# pcg_eletr.net
KiCad netlist of a schematic drawn in EAGLE
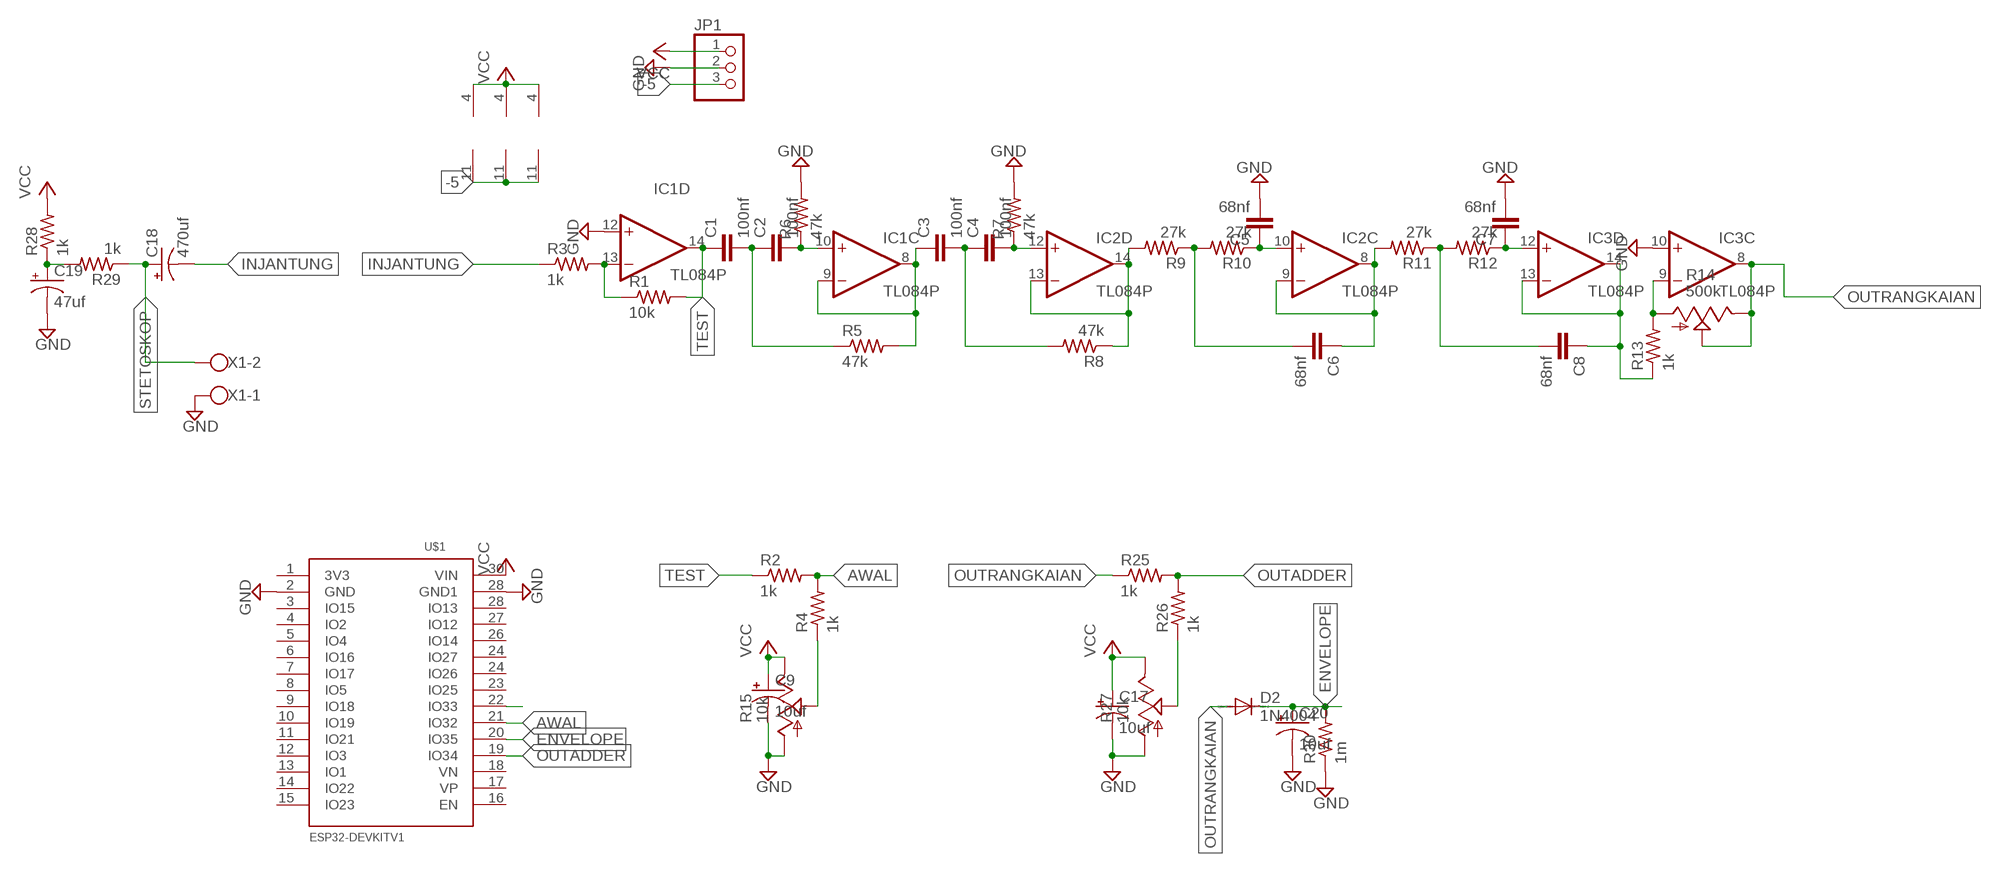
[diagram p0: schematic, sheet 1]

(export (version "E")
  (design (tool "Eeschema 10.0.6"))
  (components
    (comp (ref "C1")
      (value "100nf")
      (footprint "eagle-import:C050-025X075")
      (libsource (lib "eagle-import") (part "C-EU050-025X075"))
    )
    (comp (ref "C2")
      (value "100nf")
      (footprint "eagle-import:C050-025X075")
      (libsource (lib "eagle-import") (part "C-EU050-025X075"))
    )
    (comp (ref "C3")
      (value "100nf")
      (footprint "eagle-import:C050-025X075")
      (libsource (lib "eagle-import") (part "C-EU050-025X075"))
    )
    (comp (ref "C4")
      (value "100nf")
      (footprint "eagle-import:C050-025X075")
      (libsource (lib "eagle-import") (part "C-EU050-025X075"))
    )
    (comp (ref "C5")
      (value "68nf")
      (footprint "eagle-import:C050-025X075")
      (libsource (lib "eagle-import") (part "C-EU050-025X075"))
    )
    (comp (ref "C6")
      (value "68nf")
      (footprint "eagle-import:C050-025X075")
      (libsource (lib "eagle-import") (part "C-EU050-025X075"))
    )
    (comp (ref "C7")
      (value "68nf")
      (footprint "eagle-import:C050-025X075")
      (libsource (lib "eagle-import") (part "C-EU050-025X075"))
    )
    (comp (ref "C8")
      (value "68nf")
      (footprint "eagle-import:C050-025X075")
      (libsource (lib "eagle-import") (part "C-EU050-025X075"))
    )
    (comp (ref "C9")
      (value "10uf")
      (footprint "eagle-import:E2-5")
      (libsource (lib "eagle-import") (part "CPOL-USE2-5"))
    )
    (comp (ref "C17")
      (value "10uf")
      (footprint "eagle-import:E2-5")
      (libsource (lib "eagle-import") (part "CPOL-USE2-5"))
    )
    (comp (ref "C18")
      (value "470uf")
      (footprint "eagle-import:E2,5-7")
      (libsource (lib "eagle-import") (part "CPOL-USE2.5-7"))
    )
    (comp (ref "C19")
      (value "47uf")
      (footprint "eagle-import:E2-5")
      (libsource (lib "eagle-import") (part "CPOL-USE2-5"))
    )
    (comp (ref "C20")
      (value "10uf")
      (footprint "eagle-import:E2-5")
      (libsource (lib "eagle-import") (part "CPOL-USE2-5"))
    )
    (comp (ref "D2")
      (value "1N4004")
      (footprint "eagle-import:DO41-10")
      (libsource (lib "eagle-import") (part "1N4004"))
    )
    (comp (ref "IC1")
      (value "TL084P")
      (footprint "eagle-import:DIL14")
      (libsource (lib "eagle-import") (part "TL084P"))
    )
    (comp (ref "IC2")
      (value "TL084P")
      (footprint "eagle-import:DIL14")
      (libsource (lib "eagle-import") (part "TL084P"))
    )
    (comp (ref "IC3")
      (value "TL084P")
      (footprint "eagle-import:DIL14")
      (libsource (lib "eagle-import") (part "TL084P"))
    )
    (comp (ref "JP1")
      (value "PINHD-1X3")
      (footprint "eagle-import:1X03")
      (libsource (lib "eagle-import") (part "PINHD-1X3"))
    )
    (comp (ref "R1")
      (value "10k")
      (footprint "eagle-import:0207_7")
      (libsource (lib "eagle-import") (part "R-US_0207/7"))
    )
    (comp (ref "R2")
      (value "1k")
      (footprint "eagle-import:0207_7")
      (libsource (lib "eagle-import") (part "R-US_0207/7"))
    )
    (comp (ref "R3")
      (value "1k")
      (footprint "eagle-import:0207_7")
      (libsource (lib "eagle-import") (part "R-US_0207/7"))
    )
    (comp (ref "R4")
      (value "1k")
      (footprint "eagle-import:0207_7")
      (libsource (lib "eagle-import") (part "R-US_0207/7"))
    )
    (comp (ref "R5")
      (value "47k")
      (footprint "eagle-import:0207_7")
      (libsource (lib "eagle-import") (part "R-US_0207/7"))
    )
    (comp (ref "R6")
      (value "47k")
      (footprint "eagle-import:0207_7")
      (libsource (lib "eagle-import") (part "R-US_0207/7"))
    )
    (comp (ref "R7")
      (value "47k")
      (footprint "eagle-import:0207_7")
      (libsource (lib "eagle-import") (part "R-US_0207/7"))
    )
    (comp (ref "R8")
      (value "47k")
      (footprint "eagle-import:0207_7")
      (libsource (lib "eagle-import") (part "R-US_0207/7"))
    )
    (comp (ref "R9")
      (value "27k")
      (footprint "eagle-import:0207_7")
      (libsource (lib "eagle-import") (part "R-US_0207/7"))
    )
    (comp (ref "R10")
      (value "27k")
      (footprint "eagle-import:0207_7")
      (libsource (lib "eagle-import") (part "R-US_0207/7"))
    )
    (comp (ref "R11")
      (value "27k")
      (footprint "eagle-import:0207_7")
      (libsource (lib "eagle-import") (part "R-US_0207/7"))
    )
    (comp (ref "R12")
      (value "27k")
      (footprint "eagle-import:0207_7")
      (libsource (lib "eagle-import") (part "R-US_0207/7"))
    )
    (comp (ref "R13")
      (value "1k")
      (footprint "eagle-import:0207_7")
      (libsource (lib "eagle-import") (part "R-US_0207/7"))
    )
    (comp (ref "R14")
      (value "500k")
      (footprint "eagle-import:B64Y")
      (libsource (lib "eagle-import") (part "TRIM_US-B64Y"))
    )
    (comp (ref "R15")
      (value "10k")
      (footprint "eagle-import:B64Y")
      (libsource (lib "eagle-import") (part "TRIM_US-B64Y"))
    )
    (comp (ref "R25")
      (value "1k")
      (footprint "eagle-import:0207_7")
      (libsource (lib "eagle-import") (part "R-US_0207/7"))
    )
    (comp (ref "R26")
      (value "1k")
      (footprint "eagle-import:0207_7")
      (libsource (lib "eagle-import") (part "R-US_0207/7"))
    )
    (comp (ref "R27")
      (value "10k")
      (footprint "eagle-import:B64Y")
      (libsource (lib "eagle-import") (part "TRIM_US-B64Y"))
    )
    (comp (ref "R28")
      (value "1k")
      (footprint "eagle-import:0207_7")
      (libsource (lib "eagle-import") (part "R-US_0207/7"))
    )
    (comp (ref "R29")
      (value "1k")
      (footprint "eagle-import:0207_7")
      (libsource (lib "eagle-import") (part "R-US_0207/7"))
    )
    (comp (ref "R30")
      (value "1m")
      (footprint "eagle-import:0207_7")
      (libsource (lib "eagle-import") (part "R-US_0207/7"))
    )
    (comp (ref "U$1")
      (value "ESP32DEVKITV1")
      (footprint "eagle-import:ESP32-DEVKITV1")
      (libsource (lib "eagle-import") (part "ESP32DEVKITV1"))
    )
    (comp (ref "X1")
      (value "W237-102")
      (footprint "eagle-import:W237-102")
      (fields (field (name "MPN") "237-102"))
      (libsource (lib "eagle-import") (part "W237-102"))
    )
  )
  (nets
    (net (code "1") (name "-5") (class "Default")
      (node (ref "IC1") (pin "11") (pinfunction "V-_11") (pintype "power_in"))
      (node (ref "IC2") (pin "11") (pinfunction "V-_11") (pintype "power_in"))
      (node (ref "IC3") (pin "11") (pinfunction "V-_11") (pintype "power_in"))
      (node (ref "JP1") (pin "3") (pinfunction "3_3") (pintype "passive"))
    )
    (net (code "2") (name "AWAL") (class "Default")
      (node (ref "R2") (pin "2") (pinfunction "2_2") (pintype "passive"))
      (node (ref "R4") (pin "2") (pinfunction "2_2") (pintype "passive"))
      (node (ref "U$1") (pin "21") (pinfunction "IO32_21") (pintype "bidirectional"))
    )
    (net (code "3") (name "ENVELOPE") (class "Default")
      (node (ref "C20") (pin "+") (pinfunction "+_+") (pintype "passive"))
      (node (ref "D2") (pin "C") (pinfunction "C_C") (pintype "passive"))
      (node (ref "R30") (pin "2") (pinfunction "2_2") (pintype "passive"))
      (node (ref "U$1") (pin "20") (pinfunction "IO35_20") (pintype "bidirectional"))
    )
    (net (code "4") (name "GND") (class "Default")
      (node (ref "C17") (pin "-") (pinfunction "-_-") (pintype "passive"))
      (node (ref "C19") (pin "-") (pinfunction "-_-") (pintype "passive"))
      (node (ref "C20") (pin "-") (pinfunction "-_-") (pintype "passive"))
      (node (ref "C5") (pin "2") (pinfunction "2_2") (pintype "passive"))
      (node (ref "C7") (pin "2") (pinfunction "2_2") (pintype "passive"))
      (node (ref "C9") (pin "-") (pinfunction "-_-") (pintype "passive"))
      (node (ref "IC1") (pin "12") (pinfunction "+IN_12") (pintype "input"))
      (node (ref "IC3") (pin "10") (pinfunction "+IN_10") (pintype "input"))
      (node (ref "JP1") (pin "2") (pinfunction "2_2") (pintype "passive"))
      (node (ref "R15") (pin "A") (pinfunction "A_A") (pintype "passive"))
      (node (ref "R27") (pin "A") (pinfunction "A_A") (pintype "passive"))
      (node (ref "R30") (pin "1") (pinfunction "1_1") (pintype "passive"))
      (node (ref "R6") (pin "2") (pinfunction "2_2") (pintype "passive"))
      (node (ref "R7") (pin "2") (pinfunction "2_2") (pintype "passive"))
      (node (ref "U$1") (pin "2") (pinfunction "GND_2") (pintype "bidirectional"))
      (node (ref "U$1") (pin "28") (pinfunction "GND1_28") (pintype "bidirectional"))
      (node (ref "X1") (pin "1") (pinfunction "KL_1") (pintype "passive"))
    )
    (net (code "5") (name "INJANTUNG") (class "Default")
      (node (ref "C18") (pin "-") (pinfunction "-_-") (pintype "passive"))
      (node (ref "R3") (pin "1") (pinfunction "1_1") (pintype "passive"))
    )
    (net (code "6") (name "Net-(C1-Pad2)") (class "Default")
      (node (ref "C1") (pin "2") (pinfunction "2_2") (pintype "passive"))
      (node (ref "C2") (pin "1") (pinfunction "1_1") (pintype "passive"))
      (node (ref "R5") (pin "1") (pinfunction "1_1") (pintype "passive"))
    )
    (net (code "7") (name "Net-(C3-Pad2)") (class "Default")
      (node (ref "C3") (pin "2") (pinfunction "2_2") (pintype "passive"))
      (node (ref "C4") (pin "1") (pinfunction "1_1") (pintype "passive"))
      (node (ref "R8") (pin "2") (pinfunction "2_2") (pintype "passive"))
    )
    (net (code "8") (name "Net-(C6-Pad2)") (class "Default")
      (node (ref "C6") (pin "2") (pinfunction "2_2") (pintype "passive"))
      (node (ref "R10") (pin "2") (pinfunction "2_2") (pintype "passive"))
      (node (ref "R9") (pin "1") (pinfunction "1_1") (pintype "passive"))
    )
    (net (code "9") (name "Net-(C8-Pad2)") (class "Default")
      (node (ref "C8") (pin "2") (pinfunction "2_2") (pintype "passive"))
      (node (ref "R11") (pin "1") (pinfunction "1_1") (pintype "passive"))
      (node (ref "R12") (pin "2") (pinfunction "2_2") (pintype "passive"))
    )
    (net (code "10") (name "Net-(C19-Pad+)") (class "Default")
      (node (ref "C19") (pin "+") (pinfunction "+_+") (pintype "passive"))
      (node (ref "R28") (pin "1") (pinfunction "1_1") (pintype "passive"))
      (node (ref "R29") (pin "2") (pinfunction "2_2") (pintype "passive"))
    )
    (net (code "11") (name "Net-(IC1C-+IN)") (class "Default")
      (node (ref "C2") (pin "2") (pinfunction "2_2") (pintype "passive"))
      (node (ref "IC1") (pin "10") (pinfunction "+IN_10") (pintype "input"))
      (node (ref "R6") (pin "1") (pinfunction "1_1") (pintype "passive"))
    )
    (net (code "12") (name "Net-(IC1C--IN)") (class "Default")
      (node (ref "C3") (pin "1") (pinfunction "1_1") (pintype "passive"))
      (node (ref "IC1") (pin "8") (pinfunction "OUT_8") (pintype "output"))
      (node (ref "IC1") (pin "9") (pinfunction "-IN_9") (pintype "input"))
      (node (ref "R5") (pin "2") (pinfunction "2_2") (pintype "passive"))
    )
    (net (code "13") (name "Net-(IC1D--IN)") (class "Default")
      (node (ref "IC1") (pin "13") (pinfunction "-IN_13") (pintype "input"))
      (node (ref "R1") (pin "1") (pinfunction "1_1") (pintype "passive"))
      (node (ref "R3") (pin "2") (pinfunction "2_2") (pintype "passive"))
    )
    (net (code "14") (name "Net-(IC2C-+IN)") (class "Default")
      (node (ref "C5") (pin "1") (pinfunction "1_1") (pintype "passive"))
      (node (ref "IC2") (pin "10") (pinfunction "+IN_10") (pintype "input"))
      (node (ref "R10") (pin "1") (pinfunction "1_1") (pintype "passive"))
    )
    (net (code "15") (name "Net-(IC2C--IN)") (class "Default")
      (node (ref "C6") (pin "1") (pinfunction "1_1") (pintype "passive"))
      (node (ref "IC2") (pin "8") (pinfunction "OUT_8") (pintype "output"))
      (node (ref "IC2") (pin "9") (pinfunction "-IN_9") (pintype "input"))
      (node (ref "R11") (pin "2") (pinfunction "2_2") (pintype "passive"))
    )
    (net (code "16") (name "Net-(IC2D-+IN)") (class "Default")
      (node (ref "C4") (pin "2") (pinfunction "2_2") (pintype "passive"))
      (node (ref "IC2") (pin "12") (pinfunction "+IN_12") (pintype "input"))
      (node (ref "R7") (pin "1") (pinfunction "1_1") (pintype "passive"))
    )
    (net (code "17") (name "Net-(IC2D--IN)") (class "Default")
      (node (ref "IC2") (pin "13") (pinfunction "-IN_13") (pintype "input"))
      (node (ref "IC2") (pin "14") (pinfunction "OUT_14") (pintype "output"))
      (node (ref "R8") (pin "1") (pinfunction "1_1") (pintype "passive"))
      (node (ref "R9") (pin "2") (pinfunction "2_2") (pintype "passive"))
    )
    (net (code "18") (name "Net-(IC3C--IN)") (class "Default")
      (node (ref "IC3") (pin "9") (pinfunction "-IN_9") (pintype "input"))
      (node (ref "R13") (pin "2") (pinfunction "2_2") (pintype "passive"))
      (node (ref "R14") (pin "A") (pinfunction "A_A") (pintype "passive"))
    )
    (net (code "19") (name "Net-(IC3D-+IN)") (class "Default")
      (node (ref "C7") (pin "1") (pinfunction "1_1") (pintype "passive"))
      (node (ref "IC3") (pin "12") (pinfunction "+IN_12") (pintype "input"))
      (node (ref "R12") (pin "1") (pinfunction "1_1") (pintype "passive"))
    )
    (net (code "20") (name "Net-(IC3D--IN)") (class "Default")
      (node (ref "C8") (pin "1") (pinfunction "1_1") (pintype "passive"))
      (node (ref "IC3") (pin "13") (pinfunction "-IN_13") (pintype "input"))
      (node (ref "IC3") (pin "14") (pinfunction "OUT_14") (pintype "output"))
      (node (ref "R13") (pin "1") (pinfunction "1_1") (pintype "passive"))
    )
    (net (code "21") (name "Net-(R15-PadS)") (class "Default")
      (node (ref "R15") (pin "S") (pinfunction "S_S") (pintype "passive"))
      (node (ref "R4") (pin "1") (pinfunction "1_1") (pintype "passive"))
    )
    (net (code "22") (name "Net-(R26-Pad1)") (class "Default")
      (node (ref "R26") (pin "1") (pinfunction "1_1") (pintype "passive"))
      (node (ref "R27") (pin "S") (pinfunction "S_S") (pintype "passive"))
    )
    (net (code "23") (name "OUTADDER") (class "Default")
      (node (ref "R25") (pin "2") (pinfunction "2_2") (pintype "passive"))
      (node (ref "R26") (pin "2") (pinfunction "2_2") (pintype "passive"))
      (node (ref "U$1") (pin "19") (pinfunction "IO34_19") (pintype "bidirectional"))
    )
    (net (code "24") (name "OUTRANGKAIAN") (class "Default")
      (node (ref "D2") (pin "A") (pinfunction "A_A") (pintype "passive"))
      (node (ref "IC3") (pin "8") (pinfunction "OUT_8") (pintype "output"))
      (node (ref "R14") (pin "E") (pinfunction "E_E") (pintype "passive"))
      (node (ref "R14") (pin "S") (pinfunction "S_S") (pintype "passive"))
      (node (ref "R25") (pin "1") (pinfunction "1_1") (pintype "passive"))
    )
    (net (code "25") (name "STETOSKOP") (class "Default")
      (node (ref "C18") (pin "+") (pinfunction "+_+") (pintype "passive"))
      (node (ref "R29") (pin "1") (pinfunction "1_1") (pintype "passive"))
      (node (ref "X1") (pin "2") (pinfunction "KL_2") (pintype "passive"))
    )
    (net (code "26") (name "TEST") (class "Default")
      (node (ref "C1") (pin "1") (pinfunction "1_1") (pintype "passive"))
      (node (ref "IC1") (pin "14") (pinfunction "OUT_14") (pintype "output"))
      (node (ref "R1") (pin "2") (pinfunction "2_2") (pintype "passive"))
      (node (ref "R2") (pin "1") (pinfunction "1_1") (pintype "passive"))
    )
    (net (code "27") (name "VCC") (class "Default")
      (node (ref "C17") (pin "+") (pinfunction "+_+") (pintype "passive"))
      (node (ref "C9") (pin "+") (pinfunction "+_+") (pintype "passive"))
      (node (ref "IC1") (pin "4") (pinfunction "V+_4") (pintype "power_in"))
      (node (ref "IC2") (pin "4") (pinfunction "V+_4") (pintype "power_in"))
      (node (ref "IC3") (pin "4") (pinfunction "V+_4") (pintype "power_in"))
      (node (ref "JP1") (pin "1") (pinfunction "1_1") (pintype "passive"))
      (node (ref "R15") (pin "E") (pinfunction "E_E") (pintype "passive"))
      (node (ref "R27") (pin "E") (pinfunction "E_E") (pintype "passive"))
      (node (ref "R28") (pin "2") (pinfunction "2_2") (pintype "passive"))
      (node (ref "U$1") (pin "30") (pinfunction "VIN_30") (pintype "bidirectional"))
    )
    (net (code "28") (name "unconnected-(U$1-3V3-Pad1)") (class "Default")
      (node (ref "U$1") (pin "1") (pinfunction "3V3_1") (pintype "bidirectional"))
    )
    (net (code "29") (name "unconnected-(U$1-EN-Pad16)") (class "Default")
      (node (ref "U$1") (pin "16") (pinfunction "EN_16") (pintype "bidirectional"))
    )
    (net (code "30") (name "unconnected-(U$1-IO1-Pad13)") (class "Default")
      (node (ref "U$1") (pin "13") (pinfunction "IO1_13") (pintype "bidirectional"))
    )
    (net (code "31") (name "unconnected-(U$1-IO2-Pad4)") (class "Default")
      (node (ref "U$1") (pin "4") (pinfunction "IO2_4") (pintype "bidirectional"))
    )
    (net (code "32") (name "unconnected-(U$1-IO3-Pad12)") (class "Default")
      (node (ref "U$1") (pin "12") (pinfunction "IO3_12") (pintype "bidirectional"))
    )
    (net (code "33") (name "unconnected-(U$1-IO4-Pad5)") (class "Default")
      (node (ref "U$1") (pin "5") (pinfunction "IO4_5") (pintype "bidirectional"))
    )
    (net (code "34") (name "unconnected-(U$1-IO5-Pad8)") (class "Default")
      (node (ref "U$1") (pin "8") (pinfunction "IO5_8") (pintype "bidirectional"))
    )
    (net (code "35") (name "unconnected-(U$1-IO12-Pad27)") (class "Default")
      (node (ref "U$1") (pin "27") (pinfunction "IO12_27") (pintype "bidirectional"))
    )
    (net (code "36") (name "unconnected-(U$1-IO13-Pad28)") (class "Default")
      (node (ref "U$1") (pin "28") (pinfunction "IO13_28") (pintype "bidirectional"))
    )
    (net (code "37") (name "unconnected-(U$1-IO14-Pad26)") (class "Default")
      (node (ref "U$1") (pin "26") (pinfunction "IO14_26") (pintype "bidirectional"))
    )
    (net (code "38") (name "unconnected-(U$1-IO15-Pad3)") (class "Default")
      (node (ref "U$1") (pin "3") (pinfunction "IO15_3") (pintype "bidirectional"))
    )
    (net (code "39") (name "unconnected-(U$1-IO16-Pad6)") (class "Default")
      (node (ref "U$1") (pin "6") (pinfunction "IO16_6") (pintype "bidirectional"))
    )
    (net (code "40") (name "unconnected-(U$1-IO17-Pad7)") (class "Default")
      (node (ref "U$1") (pin "7") (pinfunction "IO17_7") (pintype "bidirectional"))
    )
    (net (code "41") (name "unconnected-(U$1-IO18-Pad9)") (class "Default")
      (node (ref "U$1") (pin "9") (pinfunction "IO18_9") (pintype "bidirectional"))
    )
    (net (code "42") (name "unconnected-(U$1-IO19-Pad10)") (class "Default")
      (node (ref "U$1") (pin "10") (pinfunction "IO19_10") (pintype "bidirectional"))
    )
    (net (code "43") (name "unconnected-(U$1-IO21-Pad11)") (class "Default")
      (node (ref "U$1") (pin "11") (pinfunction "IO21_11") (pintype "bidirectional"))
    )
    (net (code "44") (name "unconnected-(U$1-IO22-Pad14)") (class "Default")
      (node (ref "U$1") (pin "14") (pinfunction "IO22_14") (pintype "bidirectional"))
    )
    (net (code "45") (name "unconnected-(U$1-IO23-Pad15)") (class "Default")
      (node (ref "U$1") (pin "15") (pinfunction "IO23_15") (pintype "bidirectional"))
    )
    (net (code "46") (name "unconnected-(U$1-IO25-Pad23)") (class "Default")
      (node (ref "U$1") (pin "23") (pinfunction "IO25_23") (pintype "bidirectional"))
    )
    (net (code "47") (name "unconnected-(U$1-IO26-Pad24)") (class "Default")
      (node (ref "U$1") (pin "24") (pinfunction "IO26_24") (pintype "bidirectional"))
    )
    (net (code "48") (name "unconnected-(U$1-IO27-Pad24)") (class "Default")
      (node (ref "U$1") (pin "24") (pinfunction "IO27_24") (pintype "bidirectional"))
    )
    (net (code "49") (name "unconnected-(U$1-IO33-Pad22)") (class "Default")
      (node (ref "U$1") (pin "22") (pinfunction "IO33_22") (pintype "bidirectional"))
    )
    (net (code "50") (name "unconnected-(U$1-VN-Pad18)") (class "Default")
      (node (ref "U$1") (pin "18") (pinfunction "VN_18") (pintype "bidirectional"))
    )
    (net (code "51") (name "unconnected-(U$1-VP-Pad17)") (class "Default")
      (node (ref "U$1") (pin "17") (pinfunction "VP_17") (pintype "bidirectional"))
    )
  )
)
